# Power.net
KiCad netlist of a schematic drawn in Altium Designer
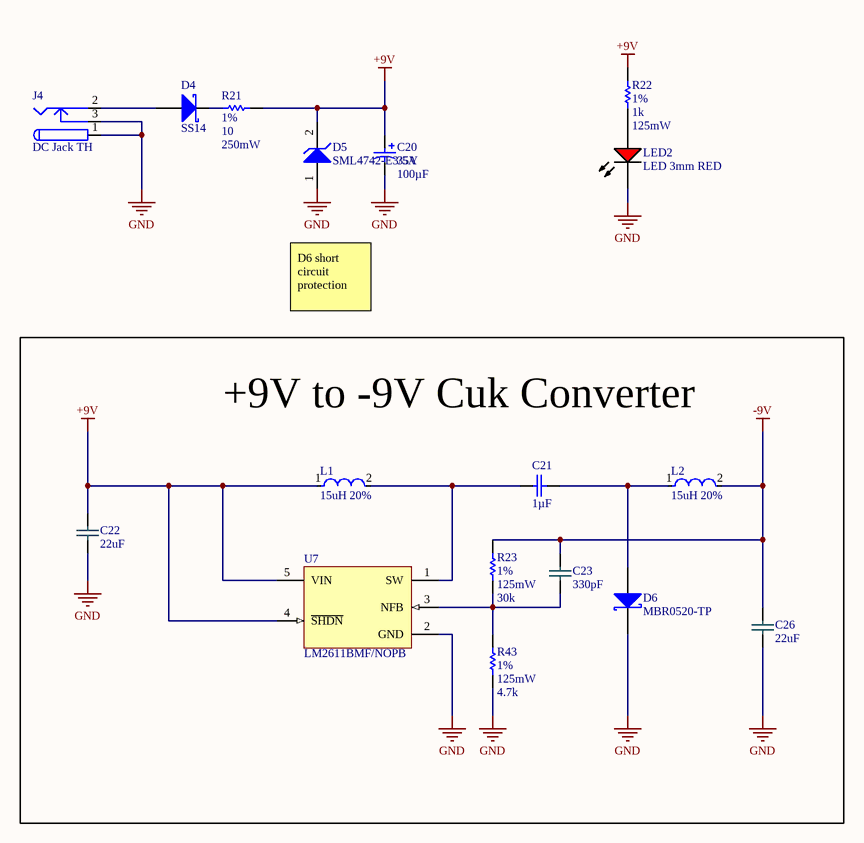
[diagram p0: Power.SchDoc]

(export (version "E")
  (design (tool "Eeschema 10.0.6"))
  (components
    (comp (ref "C20")
      (value "Cap pol 100µF 35V")
      (footprint "E-CAP, SMT, diameter 6.3mm, height 7.7mm")
      (description "Cap Aluminum 100uF 35V ±20% (6.3x7.7mm) SMD 2000h 85°C")
      (fields (field (name "RATED VOLTAGE") "35V") (field (name "CAPACITANCE") "100µF"))
      (libsource (lib "Darkglass Electronics") (part "Capacitor Polarized"))
    )
    (comp (ref "C21")
      (value "Cap 1µF 0805 X7R")
      (footprint "0805-CAP")
      (description "Cap 1µF 0805 X7R 50V +-10%")
      (fields (field (name "CAPACITANCE") "1µF"))
      (libsource (lib "Darkglass Electronics") (part "Capacitor Non-polarized"))
    )
    (comp (ref "C22")
      (value "22uF")
      (footprint "1206-CAP")
      (description "22uF, 25V, X5R, 20%")
      (fields (field (name "TOLERANCE") "20%") (field (name "Comment") "Cap 1206 22uF"))
      (libsource (lib "Darkglass Electronics") (part "Capacitor NP"))
    )
    (comp (ref "C23")
      (value "330pF")
      (footprint "0603-CAP")
      (description "330pF,  5%,  50V,  C0G")
      (fields (field (name "TOLERANCE") "5%") (field (name "VOLTAGE") "50V"))
      (libsource (lib "Darkglass Electronics") (part "Capacitor NP"))
    )
    (comp (ref "C26")
      (value "22uF")
      (footprint "1206-CAP")
      (description "22uF, 25V, X5R, 20%")
      (fields (field (name "TOLERANCE") "20%") (field (name "Comment") "Cap 1206 22uF"))
      (libsource (lib "Darkglass Electronics") (part "Capacitor NP"))
    )
    (comp (ref "D4")
      (value "SS14")
      (footprint "SS14")
      (description "ON SEMICONDUCTOR - SS14 - DIODE, SCHOTTKY, 1A, 40V, DO-214AC-2")
      (fields (field (name "MANUFACTURER") "ON Semiconductor / Fairchild") (field (name "VOLTAGE") "40V"))
      (libsource (lib "") (part "SS14_1"))
    )
    (comp (ref "D5")
      (value "SML4742-E3/5A")
      (footprint "DO-214AC")
      (description "12V Zener")
      (fields (field (name "TOLERANCE") "10%") (field (name "MANUFACTURER") "Vishay Semiconductors"))
      (libsource (lib "") (part "Symbol_1"))
    )
    (comp (ref "D6")
      (value "MBR0520-TP")
      (footprint "SODFL370X135-2N")
      (description "Rectifier Diode, Schottky, 1 Phase, 1 Element, 0.5A, 20V V(RRM), Silicon")
      (libsource (lib "Darkglass Electronics") (part "SS14"))
    )
    (comp (ref "J4")
      (value "DC Jack TH")
      (footprint "DC_Jack")
      (description "Low Voltage Power Supply Connector")
      (fields (field (name "DARKGLASS PART") "D00-0019"))
      (libsource (lib "Darkglass Electronics") (part "Symbol"))
    )
    (comp (ref "L1")
      (value "15uH 20%")
      (footprint "1210 SMD Cap")
      (description "Fixed Inductors 15uH 20% 0.48ohm 0.98A AEC-Q200")
      (libsource (lib "Darkglass Electronics") (part "725321dda6339637d4d059423bc1c3c"))
    )
    (comp (ref "L2")
      (value "15uH 20%")
      (footprint "1210 SMD Cap")
      (description "Fixed Inductors 15uH 20% 0.48ohm 0.98A AEC-Q200")
      (libsource (lib "Darkglass Electronics") (part "725321dda6339637d4d059423bc1c3c"))
    )
    (comp (ref "LED2")
      (value "LED 3mm RED")
      (footprint "KING-WP710A10QBCD_V")
      (description "THT LED round mono-color waterclear, WL-TMRW , RED")
      (fields
        (field (name "PARTNUMBER") "151034rs03000")
        (field (name "MANUFACTURER") "Wuerth Elektronik")
        (field (name "AVAILABLE PREVIEW IMAGES") "2D")
      )
      (libsource (lib "Darkglass Electronics") (part "LED 3mm RED"))
    )
    (comp (ref "R21")
      (value "Res 10R 1% 1206")
      (footprint "1206-RES")
      (description "Resistor 10R +-1% 1206 Thin film 0.25W +-50ppm/°C")
      (fields
        (field (name "TOLERANCE (+-)") "1%")
        (field (name "RESISTANCE") "10")
        (field (name "POWER") "250mW")
      )
      (libsource (lib "Darkglass Electronics") (part "Resistor"))
    )
    (comp (ref "R22")
      (value "Res 1k 1% 0805")
      (footprint "0805-RES")
      (description "Resistor 1k +-1% 0805 Thin film 0.125W +-50ppm/°C")
      (fields
        (field (name "TOLERANCE (+-)") "1%")
        (field (name "RESISTANCE") "1k")
        (field (name "POWER") "125mW")
      )
      (libsource (lib "Darkglass Electronics") (part "Resistor"))
    )
    (comp (ref "R23")
      (value "Res 30k 1% 0805")
      (footprint "0805-RES")
      (description "Resistor 30k +-1% 0805 Thin film 0.125W +-50ppm/°C")
      (fields
        (field (name "TOLERANCE (+-)") "1%")
        (field (name "POWER") "125mW")
        (field (name "RESISTANCE") "30k")
      )
      (libsource (lib "Darkglass Electronics") (part "Resistor"))
    )
    (comp (ref "R43")
      (value "Res 4.7k 1% 0805")
      (footprint "0805-RES")
      (description "Resistor 4.7k +-1% 0805 Thin film 0.125W +-50ppm/°C")
      (fields
        (field (name "TOLERANCE (+-)") "1%")
        (field (name "POWER") "125mW")
        (field (name "RESISTANCE") "4.7k")
      )
      (libsource (lib "Darkglass Electronics") (part "Resistor"))
    )
    (comp (ref "U7")
      (value "LM2611BMF/NOPB")
      (footprint "DBV0005A_M")
      (description "1.4MHz Cuk Converter, 5-pin SOT-23, Pb-Free")
      (fields (field (name "MANUFACTURER") "Texas Instruments"))
      (libsource (lib "Altium Content Vault") (part "PM-DCDC-LM2611"))
    )
  )
  (nets
    (net (code "1") (name "+9V") (class "Default")
      (node (ref "C20") (pin "1") (pinfunction "1_1") (pintype "passive"))
      (node (ref "C22") (pin "2") (pinfunction "2_2") (pintype "passive"))
      (node (ref "D5") (pin "2") (pinfunction "2_2") (pintype "passive"))
      (node (ref "L1") (pin "1") (pinfunction "1_1") (pintype "passive"))
      (node (ref "R21") (pin "2") (pinfunction "2_2") (pintype "passive"))
      (node (ref "R22") (pin "2") (pinfunction "2_2") (pintype "passive"))
      (node (ref "U7") (pin "4") (pinfunction "~{SHDN}_4") (pintype "input"))
      (node (ref "U7") (pin "5") (pinfunction "VIN_5") (pintype "power_in"))
    )
    (net (code "2") (name "-9V") (class "Default")
      (node (ref "C23") (pin "2") (pinfunction "2_2") (pintype "passive"))
      (node (ref "C26") (pin "2") (pinfunction "2_2") (pintype "passive"))
      (node (ref "L2") (pin "2") (pinfunction "2_2") (pintype "passive"))
      (node (ref "R23") (pin "2") (pinfunction "2_2") (pintype "passive"))
    )
    (net (code "3") (name "GND") (class "Default")
      (node (ref "C20") (pin "2") (pinfunction "2_2") (pintype "passive"))
      (node (ref "C22") (pin "1") (pinfunction "1_1") (pintype "passive"))
      (node (ref "C26") (pin "1") (pinfunction "1_1") (pintype "passive"))
      (node (ref "D5") (pin "1") (pinfunction "1_1") (pintype "passive"))
      (node (ref "D6") (pin "2") (pinfunction "K_2") (pintype "passive"))
      (node (ref "J4") (pin "1") (pinfunction "1_1") (pintype "power_in"))
      (node (ref "J4") (pin "3") (pinfunction "3_3") (pintype "power_in"))
      (node (ref "LED2") (pin "2") (pinfunction "K_2") (pintype "passive"))
      (node (ref "R43") (pin "2") (pinfunction "2_2") (pintype "passive"))
      (node (ref "U7") (pin "2") (pinfunction "GND_2") (pintype "power_in"))
    )
    (net (code "4") (name "Net-(D4-PadA)") (class "Default")
      (node (ref "D4") (pin "A") (pinfunction "A_A") (pintype "passive"))
      (node (ref "J4") (pin "2") (pinfunction "2_2") (pintype "power_in"))
    )
    (net (code "5") (name "Net-(D4-PadK)") (class "Default")
      (node (ref "D4") (pin "K") (pinfunction "K_K") (pintype "passive"))
      (node (ref "R21") (pin "1") (pinfunction "1_1") (pintype "passive"))
    )
    (net (code "6") (name "Net-(D6-A)") (class "Default")
      (node (ref "C21") (pin "2") (pinfunction "2_2") (pintype "passive"))
      (node (ref "D6") (pin "1") (pinfunction "A_1") (pintype "passive"))
      (node (ref "L2") (pin "1") (pinfunction "1_1") (pintype "passive"))
    )
    (net (code "7") (name "Net-(LED2-A)") (class "Default")
      (node (ref "LED2") (pin "1") (pinfunction "A_1") (pintype "passive"))
      (node (ref "R22") (pin "1") (pinfunction "1_1") (pintype "passive"))
    )
    (net (code "8") (name "Net-(U7-NFB)") (class "Default")
      (node (ref "C23") (pin "1") (pinfunction "1_1") (pintype "passive"))
      (node (ref "R23") (pin "1") (pinfunction "1_1") (pintype "passive"))
      (node (ref "R43") (pin "1") (pinfunction "1_1") (pintype "passive"))
      (node (ref "U7") (pin "3") (pinfunction "NFB_3") (pintype "input"))
    )
    (net (code "9") (name "Net-(U7-SW)") (class "Default")
      (node (ref "C21") (pin "1") (pinfunction "1_1") (pintype "passive"))
      (node (ref "L1") (pin "2") (pinfunction "2_2") (pintype "passive"))
      (node (ref "U7") (pin "1") (pinfunction "SW_1") (pintype "power_in"))
    )
  )
)
